# ProPrj_DBE_MosFet_15F_2025-01-06.net
KiCad netlist of a schematic drawn in EasyEDA Pro
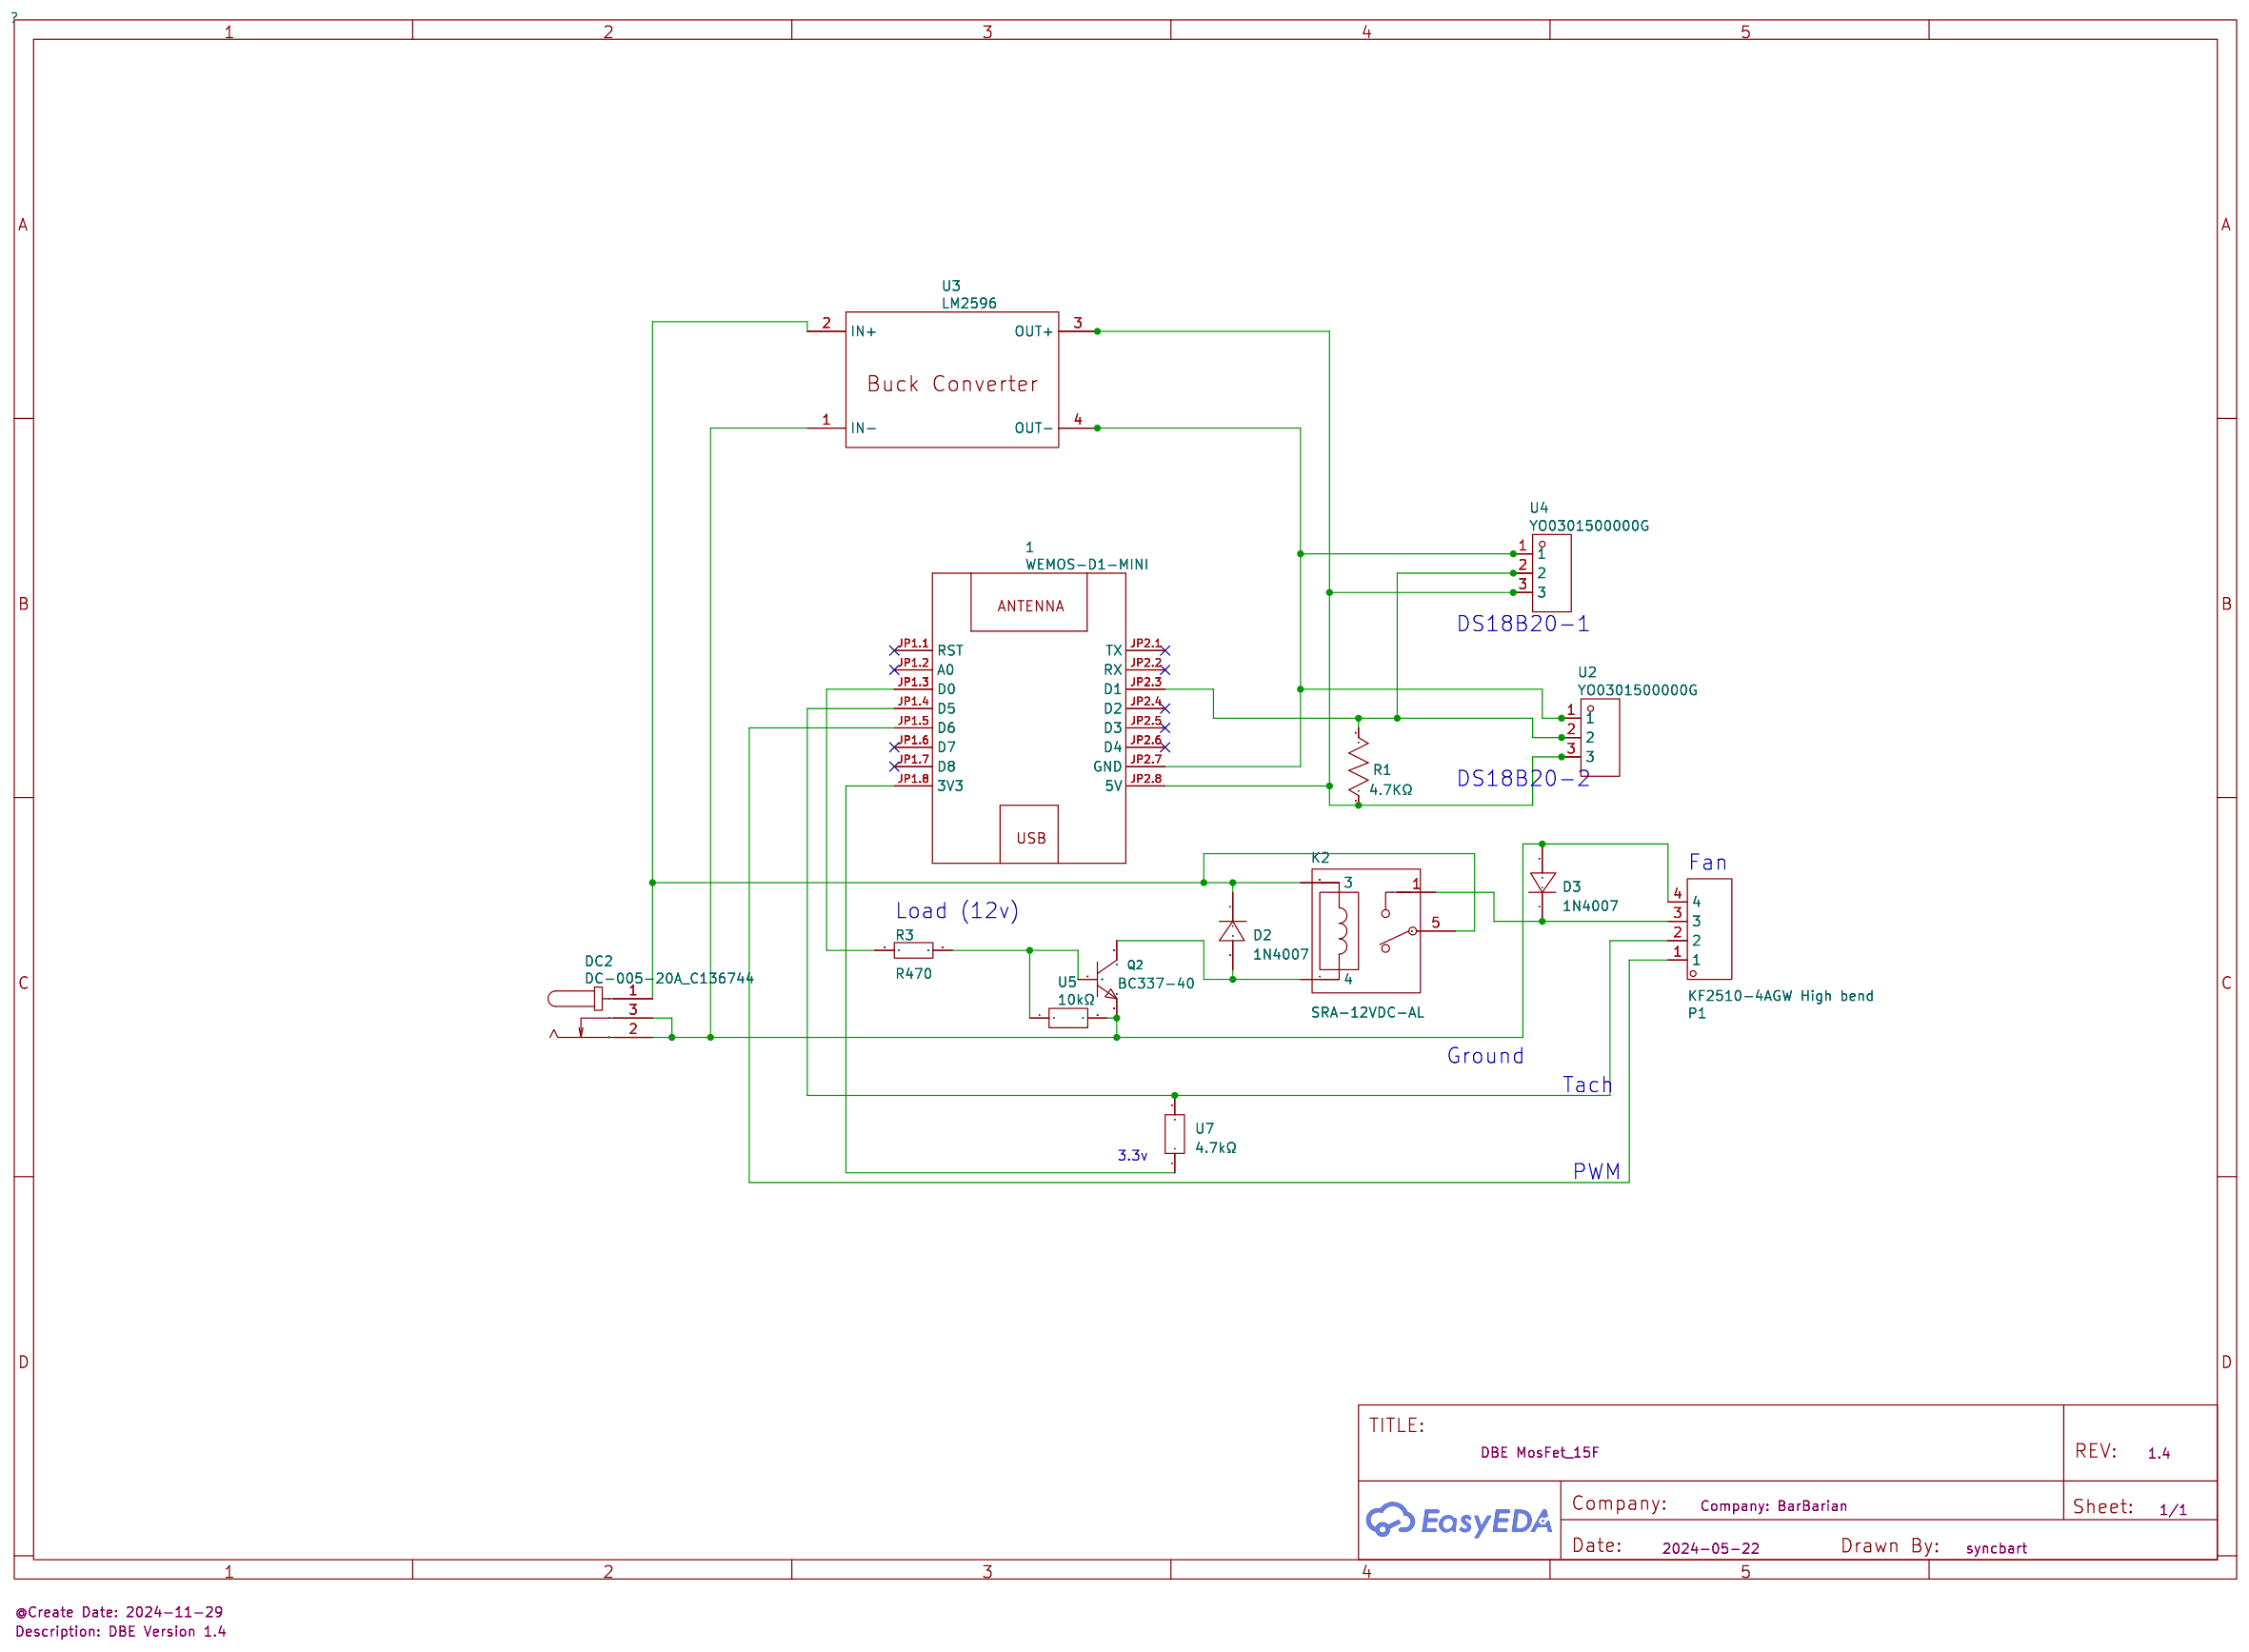
[diagram p0: schematic sheet]

(export (version "E")
  (design (tool "Eeschema 10.0.6"))
  (components
    (comp (ref "1")
      (value "WEMOS-D1-MINI")
      (footprint "easyedapro:WEMOS-D1-MINI")
      (libsource (lib "easyedapro") (part "WEMOS-D1-MINI"))
    )
    (comp (ref "D2")
      (value "1N4007")
      (footprint "easyedapro:DO-41_BD2.4-L4.7-P8.70-D0.9-RD")
      (fields (field (name "Manufacturer") "ST(先科)"))
      (libsource (lib "easyedapro") (part "1N4007"))
    )
    (comp (ref "D3")
      (value "1N4007")
      (footprint "easyedapro:DO-41_BD2.4-L4.7-P8.70-D0.9-RD")
      (fields (field (name "Manufacturer") "ST(先科)"))
      (libsource (lib "easyedapro") (part "1N4007"))
    )
    (comp (ref "DC2")
      (value "DC-005-20A_C136744")
      (footprint "easyedapro:DC-IN-TH_DC-005-20A")
      (fields (field (name "Manufacturer Part") "DC-005-20A") (field (name "Manufacturer") "韩国韩荣"))
      (libsource (lib "easyedapro") (part "DC-005-20A_C136744"))
    )
    (comp (ref "K2")
      (value "SRA-12VDC-AL")
      (footprint "easyedapro:RELAY-TH_SRA-XXVDC-AL")
      (fields (field (name "Manufacturer") "松乐"))
      (libsource (lib "easyedapro") (part "SRA-12VDC-AL"))
    )
    (comp (ref "P1")
      (value "KF2510-4AGW High bend")
      (footprint "easyedapro:CONN-TH_KF2510-4AGW")
      (fields (field (name "Manufacturer Part") "2510-4A高弯") (field (name "Manufacturer") "BOOMELE(博穆精密)"))
      (libsource (lib "easyedapro") (part "KF2510-4AGW High bend"))
    )
    (comp (ref "Q2")
      (value "BC337-40")
      (footprint "easyedapro:TO-92-3_L4.9-W3.7-P1.27-L")
      (fields (field (name "Manufacturer") "LGE(鲁光)"))
      (libsource (lib "easyedapro") (part "BC337-40"))
    )
    (comp (ref "R1")
      (value "4.7KΩ")
      (footprint "easyedapro:R0603")
      (libsource (lib "easyedapro") (part "4.7KΩ"))
    )
    (comp (ref "R3")
      (value "300mΩ")
      (footprint "easyedapro:R2512")
      (fields (field (name "Manufacturer Part") "SR73W3ATTER300F") (field (name "Manufacturer") "KOA"))
      (libsource (lib "easyedapro") (part "SR73W3ATTER300F"))
    )
    (comp (ref "U2")
      (value "YO0301500000G")
      (footprint "easyedapro:CONN-TH_YO0301500000G")
      (fields (field (name "Manufacturer") "Amphenol"))
      (libsource (lib "easyedapro") (part "YO0301500000G"))
    )
    (comp (ref "U3")
      (value "LM2596")
      (footprint "easyedapro:LM2596")
      (libsource (lib "easyedapro") (part "LM2596"))
    )
    (comp (ref "U4")
      (value "YO0301500000G")
      (footprint "easyedapro:CONN-TH_YO0301500000G")
      (fields (field (name "Manufacturer") "Amphenol"))
      (libsource (lib "easyedapro") (part "YO0301500000G"))
    )
    (comp (ref "U5")
      (value "10kΩ")
      (footprint "easyedapro:R1206")
      (fields (field (name "Manufacturer Part") "RTX061002BDTP") (field (name "Manufacturer") "RALEC(旺诠)"))
      (libsource (lib "easyedapro") (part "10kΩ"))
    )
    (comp (ref "U7")
      (value "4.7kΩ")
      (footprint "easyedapro:RES-TH_BD2.4-L6.3-P10.30-D0.6")
      (fields (field (name "Manufacturer Part") "MFR-25FBF52-13K3") (field (name "Manufacturer") "YAGEO(国巨)"))
      (libsource (lib "easyedapro") (part "MFR-25FBF52-13K3"))
    )
  )
  (nets
    (net (code "1") (name "Net-(1-3V3)") (class "Default")
      (node (ref "1") (pin "JP1.8") (pinfunction "3V3_JP1.8") (pintype "bidirectional"))
      (node (ref "U7") (pin "1") (pinfunction "1_1") (pintype "unspecified"))
    )
    (net (code "2") (name "Net-(1-5V)") (class "Default")
      (node (ref "1") (pin "JP2.8") (pinfunction "5V_JP2.8") (pintype "bidirectional"))
      (node (ref "R1") (pin "1") (pinfunction "1_1") (pintype "unspecified"))
      (node (ref "U2") (pin "3") (pinfunction "3_3") (pintype "unspecified"))
      (node (ref "U3") (pin "3") (pinfunction "OUT+_3") (pintype "unspecified"))
      (node (ref "U4") (pin "3") (pinfunction "3_3") (pintype "unspecified"))
    )
    (net (code "3") (name "Net-(1-D0)") (class "Default")
      (node (ref "1") (pin "JP1.3") (pinfunction "D0_JP1.3") (pintype "bidirectional"))
      (node (ref "R3") (pin "1") (pinfunction "1_1") (pintype "input"))
    )
    (net (code "4") (name "Net-(1-D1)") (class "Default")
      (node (ref "1") (pin "JP2.3") (pinfunction "D1_JP2.3") (pintype "bidirectional"))
      (node (ref "R1") (pin "2") (pinfunction "2_2") (pintype "unspecified"))
      (node (ref "U2") (pin "2") (pinfunction "2_2") (pintype "unspecified"))
      (node (ref "U4") (pin "2") (pinfunction "2_2") (pintype "unspecified"))
    )
    (net (code "5") (name "Net-(1-D5)") (class "Default")
      (node (ref "1") (pin "JP1.4") (pinfunction "D5_JP1.4") (pintype "bidirectional"))
      (node (ref "P1") (pin "2") (pinfunction "2_2") (pintype "unspecified"))
      (node (ref "U7") (pin "2") (pinfunction "2_2") (pintype "unspecified"))
    )
    (net (code "6") (name "Net-(1-D6)") (class "Default")
      (node (ref "1") (pin "JP1.5") (pinfunction "D6_JP1.5") (pintype "bidirectional"))
      (node (ref "P1") (pin "1") (pinfunction "1_1") (pintype "unspecified"))
    )
    (net (code "7") (name "Net-(1-GND)") (class "Default")
      (node (ref "1") (pin "JP2.7") (pinfunction "GND_JP2.7") (pintype "bidirectional"))
      (node (ref "U2") (pin "1") (pinfunction "1_1") (pintype "unspecified"))
      (node (ref "U3") (pin "4") (pinfunction "OUT-_4") (pintype "unspecified"))
      (node (ref "U4") (pin "1") (pinfunction "1_1") (pintype "unspecified"))
    )
    (net (code "8") (name "Net-(D2-A)") (class "Default")
      (node (ref "D2") (pin "2") (pinfunction "A_2") (pintype "unspecified"))
      (node (ref "K2") (pin "4") (pinfunction "4_4") (pintype "input"))
      (node (ref "Q2") (pin "1") (pinfunction "C_1") (pintype "input"))
    )
    (net (code "9") (name "Net-(D2-K)") (class "Default")
      (node (ref "D2") (pin "1") (pinfunction "K_1") (pintype "unspecified"))
      (node (ref "DC2") (pin "1") (pinfunction "1_1") (pintype "unspecified"))
      (node (ref "K2") (pin "3") (pinfunction "3_3") (pintype "input"))
      (node (ref "K2") (pin "5") (pinfunction "5_5") (pintype "input"))
      (node (ref "U3") (pin "2") (pinfunction "IN+_2") (pintype "unspecified"))
    )
    (net (code "10") (name "Net-(D3-A)") (class "Default")
      (node (ref "D3") (pin "2") (pinfunction "A_2") (pintype "unspecified"))
      (node (ref "DC2") (pin "2") (pinfunction "2_2") (pintype "unspecified"))
      (node (ref "DC2") (pin "3") (pinfunction "3_3") (pintype "unspecified"))
      (node (ref "P1") (pin "4") (pinfunction "4_4") (pintype "unspecified"))
      (node (ref "Q2") (pin "3") (pinfunction "E_3") (pintype "input"))
      (node (ref "U3") (pin "1") (pinfunction "IN-_1") (pintype "unspecified"))
      (node (ref "U5") (pin "2") (pinfunction "2_2") (pintype "unspecified"))
    )
    (net (code "11") (name "Net-(D3-K)") (class "Default")
      (node (ref "D3") (pin "1") (pinfunction "K_1") (pintype "unspecified"))
      (node (ref "K2") (pin "1") (pinfunction "1_1") (pintype "input"))
      (node (ref "P1") (pin "3") (pinfunction "3_3") (pintype "unspecified"))
    )
    (net (code "12") (name "Net-(Q2-B)") (class "Default")
      (node (ref "Q2") (pin "2") (pinfunction "B_2") (pintype "input"))
      (node (ref "R3") (pin "2") (pinfunction "2_2") (pintype "input"))
      (node (ref "U5") (pin "1") (pinfunction "1_1") (pintype "unspecified"))
    )
    (net (code "13") (name "unconnected-(1-A0-PadJP1.2)") (class "Default")
      (node (ref "1") (pin "JP1.2") (pinfunction "A0_JP1.2") (pintype "bidirectional+no_connect"))
    )
    (net (code "14") (name "unconnected-(1-D2-PadJP2.4)") (class "Default")
      (node (ref "1") (pin "JP2.4") (pinfunction "D2_JP2.4") (pintype "bidirectional+no_connect"))
    )
    (net (code "15") (name "unconnected-(1-D3-PadJP2.5)") (class "Default")
      (node (ref "1") (pin "JP2.5") (pinfunction "D3_JP2.5") (pintype "bidirectional+no_connect"))
    )
    (net (code "16") (name "unconnected-(1-D4-PadJP2.6)") (class "Default")
      (node (ref "1") (pin "JP2.6") (pinfunction "D4_JP2.6") (pintype "bidirectional+no_connect"))
    )
    (net (code "17") (name "unconnected-(1-D7-PadJP1.6)") (class "Default")
      (node (ref "1") (pin "JP1.6") (pinfunction "D7_JP1.6") (pintype "bidirectional+no_connect"))
    )
    (net (code "18") (name "unconnected-(1-D8-PadJP1.7)") (class "Default")
      (node (ref "1") (pin "JP1.7") (pinfunction "D8_JP1.7") (pintype "bidirectional+no_connect"))
    )
    (net (code "19") (name "unconnected-(1-RST-PadJP1.1)") (class "Default")
      (node (ref "1") (pin "JP1.1") (pinfunction "RST_JP1.1") (pintype "bidirectional+no_connect"))
    )
    (net (code "20") (name "unconnected-(1-RX-PadJP2.2)") (class "Default")
      (node (ref "1") (pin "JP2.2") (pinfunction "RX_JP2.2") (pintype "bidirectional+no_connect"))
    )
    (net (code "21") (name "unconnected-(1-TX-PadJP2.1)") (class "Default")
      (node (ref "1") (pin "JP2.1") (pinfunction "TX_JP2.1") (pintype "bidirectional+no_connect"))
    )
  )
)
